# 3da.net
KiCad netlist of a schematic drawn in EAGLE
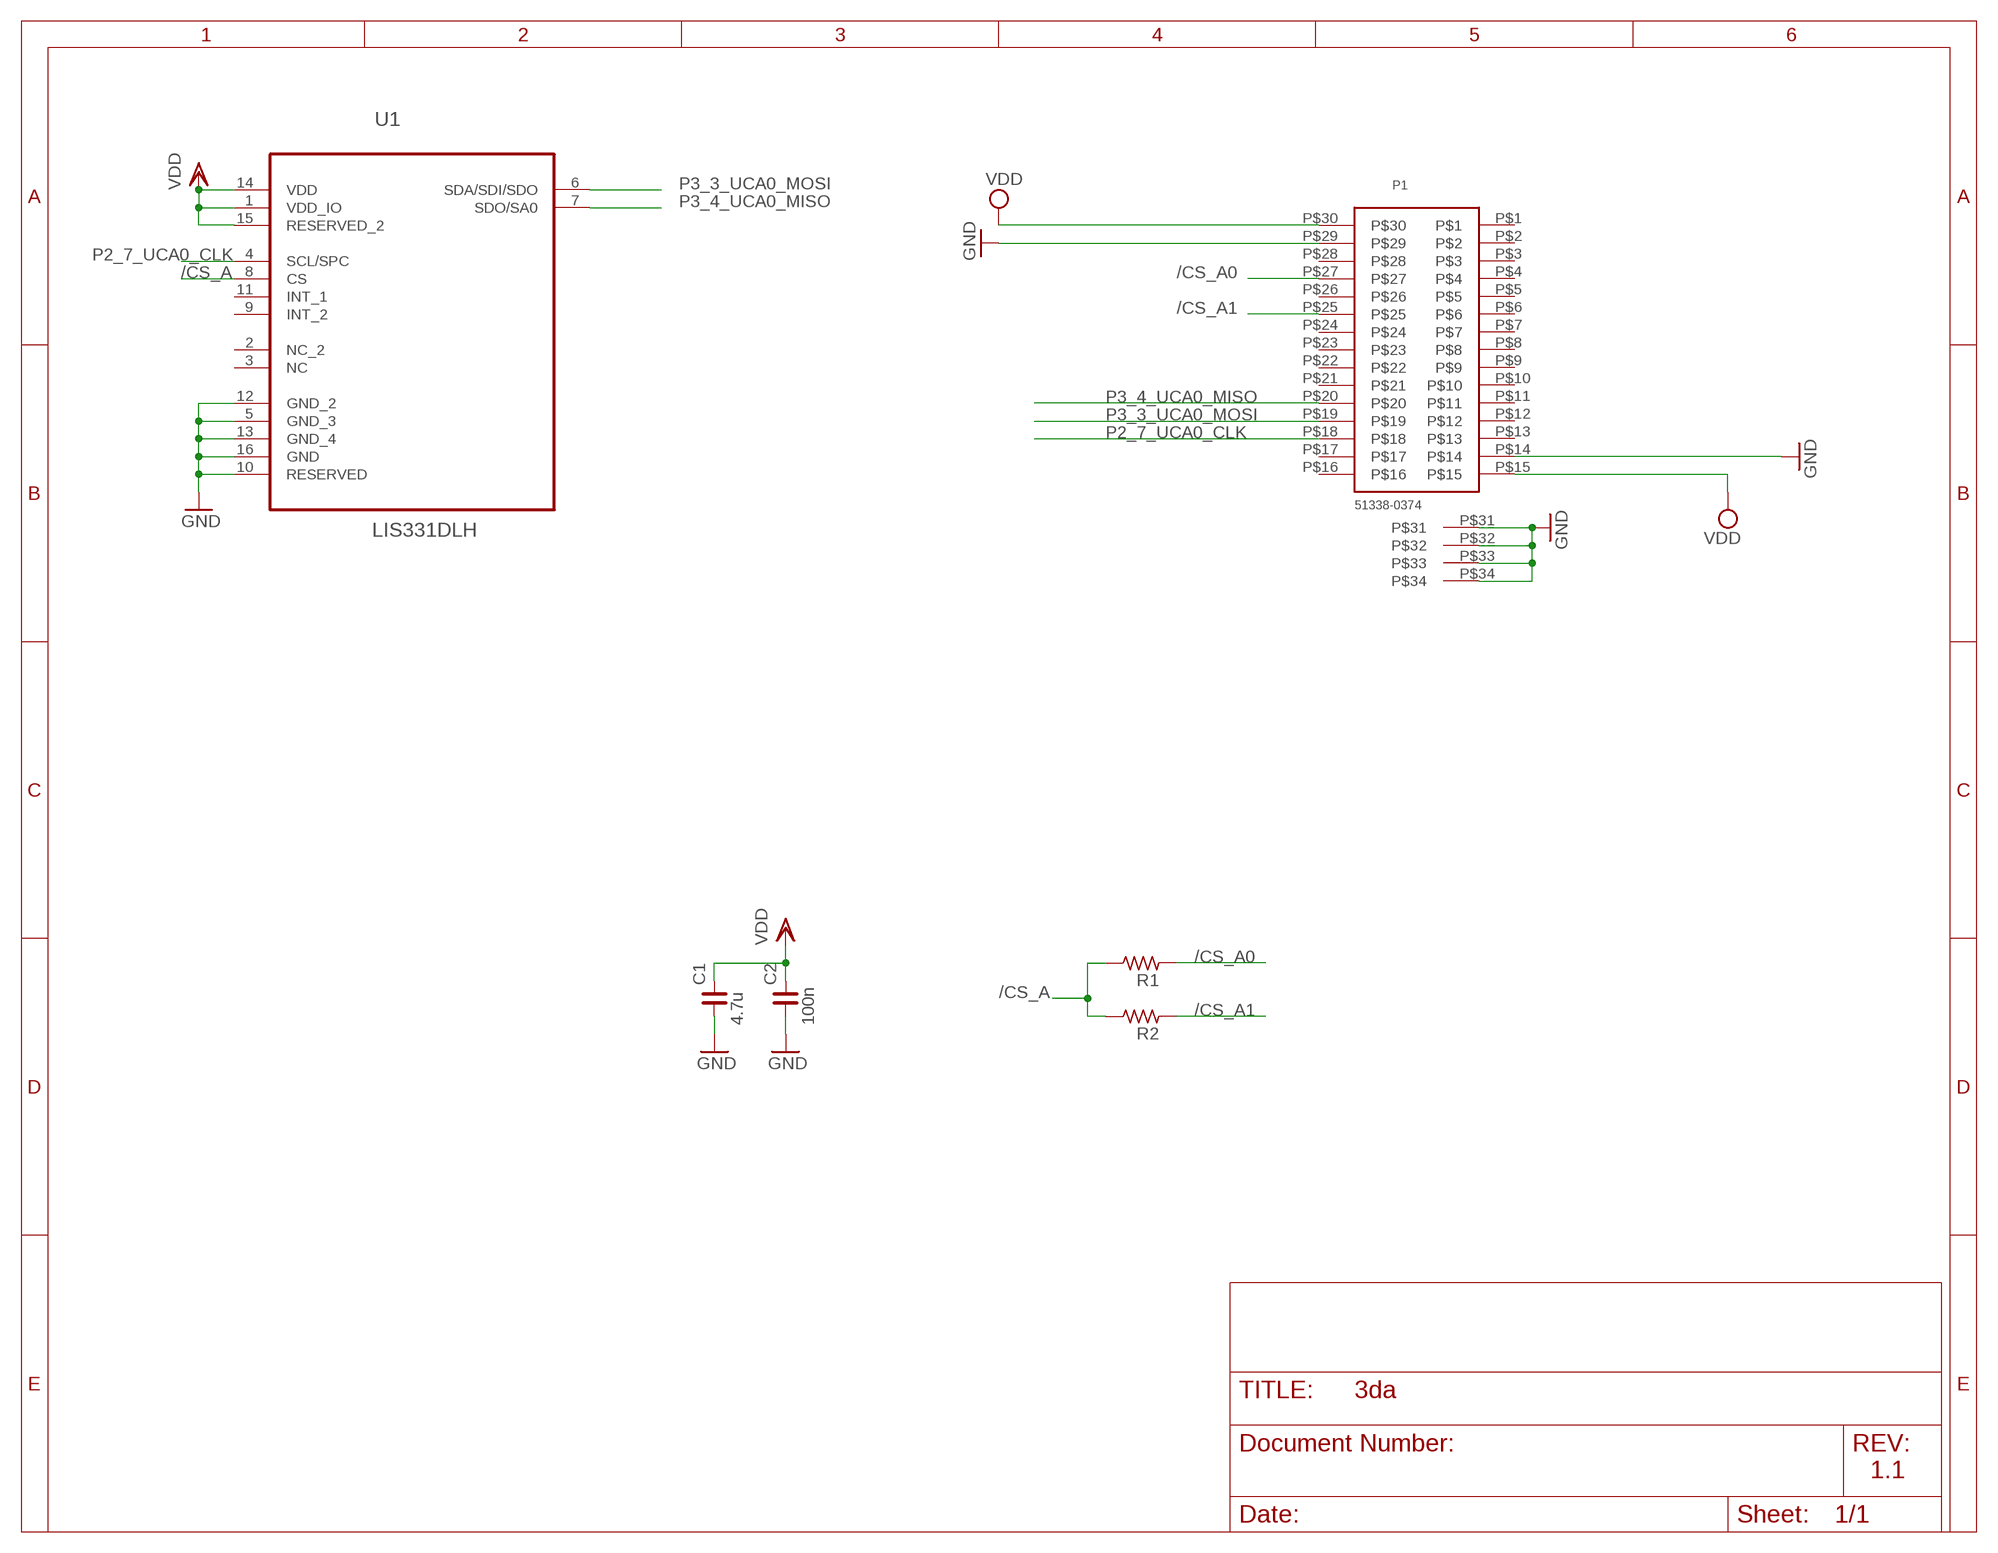
[diagram p0: schematic, sheet 1]

(export (version "E")
  (design (tool "Eeschema 10.0.6"))
  (components
    (comp (ref "C1")
      (value "4.7u")
      (footprint "eagle-import:C0402")
      (libsource (lib "eagle-import") (part "C_0402"))
    )
    (comp (ref "C2")
      (value "100n")
      (footprint "eagle-import:C0402")
      (libsource (lib "eagle-import") (part "C_0402"))
    )
    (comp (ref "P1")
      (value "51338-0374")
      (footprint "eagle-import:51338-0374_RECEPTACLE")
      (libsource (lib "eagle-import") (part "51338-0374_RECEPTACLE"))
    )
    (comp (ref "R1")
      (value "R_0402")
      (footprint "eagle-import:R0402")
      (libsource (lib "eagle-import") (part "R_0402"))
    )
    (comp (ref "R2")
      (value "R_0402")
      (footprint "eagle-import:R0402")
      (libsource (lib "eagle-import") (part "R_0402"))
    )
    (comp (ref "U1")
      (value "LIS331DLH")
      (footprint "eagle-import:LGA16R50P3X5_300X300X100")
      (libsource (lib "eagle-import") (part "LIS331DLH"))
    )
  )
  (nets
    (net (code "1") (name "/P2_7_UCA0_CLK") (class "Default")
      (node (ref "P1") (pin "P$18") (pinfunction "P$18_P$18") (pintype "bidirectional"))
      (node (ref "U1") (pin "4") (pinfunction "SCL/SPC_4") (pintype "input"))
    )
    (net (code "2") (name "/P3_3_UCA0_MOSI") (class "Default")
      (node (ref "P1") (pin "P$19") (pinfunction "P$19_P$19") (pintype "bidirectional"))
      (node (ref "U1") (pin "6") (pinfunction "SDA/SDI/SDO_6") (pintype "bidirectional"))
    )
    (net (code "3") (name "/P3_4_UCA0_MISO") (class "Default")
      (node (ref "P1") (pin "P$20") (pinfunction "P$20_P$20") (pintype "bidirectional"))
      (node (ref "U1") (pin "7") (pinfunction "SDO/SA0_7") (pintype "output"))
    )
    (net (code "4") (name "/{slash}CS_A") (class "Default")
      (node (ref "R1") (pin "2") (pinfunction "2_2") (pintype "passive"))
      (node (ref "R2") (pin "2") (pinfunction "2_2") (pintype "passive"))
      (node (ref "U1") (pin "8") (pinfunction "CS_8") (pintype "input"))
    )
    (net (code "5") (name "/{slash}CS_A0") (class "Default")
      (node (ref "P1") (pin "P$27") (pinfunction "P$27_P$27") (pintype "bidirectional"))
      (node (ref "R1") (pin "1") (pinfunction "1_1") (pintype "passive"))
    )
    (net (code "6") (name "/{slash}CS_A1") (class "Default")
      (node (ref "P1") (pin "P$25") (pinfunction "P$25_P$25") (pintype "bidirectional"))
      (node (ref "R2") (pin "1") (pinfunction "1_1") (pintype "passive"))
    )
    (net (code "7") (name "GND") (class "Default")
      (node (ref "C1") (pin "1") (pinfunction "1_1") (pintype "passive"))
      (node (ref "C2") (pin "1") (pinfunction "1_1") (pintype "passive"))
      (node (ref "P1") (pin "P$14") (pinfunction "P$14_P$14") (pintype "bidirectional"))
      (node (ref "P1") (pin "P$29") (pinfunction "P$29_P$29") (pintype "bidirectional"))
      (node (ref "P1") (pin "P$31") (pinfunction "P$31_P$31") (pintype "bidirectional"))
      (node (ref "P1") (pin "P$32") (pinfunction "P$32_P$32") (pintype "bidirectional"))
      (node (ref "P1") (pin "P$33") (pinfunction "P$33_P$33") (pintype "bidirectional"))
      (node (ref "P1") (pin "P$34") (pinfunction "P$34_P$34") (pintype "bidirectional"))
      (node (ref "U1") (pin "10") (pinfunction "RESERVED_10") (pintype "passive"))
      (node (ref "U1") (pin "12") (pinfunction "GND_2_12") (pintype "passive"))
      (node (ref "U1") (pin "13") (pinfunction "GND_4_13") (pintype "passive"))
      (node (ref "U1") (pin "16") (pinfunction "GND_16") (pintype "passive"))
      (node (ref "U1") (pin "5") (pinfunction "GND_3_5") (pintype "passive"))
    )
    (net (code "8") (name "VDD") (class "Default")
      (node (ref "C1") (pin "2") (pinfunction "2_2") (pintype "passive"))
      (node (ref "C2") (pin "2") (pinfunction "2_2") (pintype "passive"))
      (node (ref "P1") (pin "P$15") (pinfunction "P$15_P$15") (pintype "bidirectional"))
      (node (ref "P1") (pin "P$30") (pinfunction "P$30_P$30") (pintype "bidirectional"))
      (node (ref "U1") (pin "1") (pinfunction "VDD_IO_1") (pintype "power_in"))
      (node (ref "U1") (pin "14") (pinfunction "VDD_14") (pintype "power_in"))
      (node (ref "U1") (pin "15") (pinfunction "RESERVED_2_15") (pintype "power_in"))
    )
    (net (code "9") (name "unconnected-(P1-PadP$1)") (class "Default")
      (node (ref "P1") (pin "P$1") (pinfunction "P$1_P$1") (pintype "bidirectional"))
    )
    (net (code "10") (name "unconnected-(P1-PadP$2)") (class "Default")
      (node (ref "P1") (pin "P$2") (pinfunction "P$2_P$2") (pintype "bidirectional"))
    )
    (net (code "11") (name "unconnected-(P1-PadP$3)") (class "Default")
      (node (ref "P1") (pin "P$3") (pinfunction "P$3_P$3") (pintype "bidirectional"))
    )
    (net (code "12") (name "unconnected-(P1-PadP$4)") (class "Default")
      (node (ref "P1") (pin "P$4") (pinfunction "P$4_P$4") (pintype "bidirectional"))
    )
    (net (code "13") (name "unconnected-(P1-PadP$5)") (class "Default")
      (node (ref "P1") (pin "P$5") (pinfunction "P$5_P$5") (pintype "bidirectional"))
    )
    (net (code "14") (name "unconnected-(P1-PadP$6)") (class "Default")
      (node (ref "P1") (pin "P$6") (pinfunction "P$6_P$6") (pintype "bidirectional"))
    )
    (net (code "15") (name "unconnected-(P1-PadP$7)") (class "Default")
      (node (ref "P1") (pin "P$7") (pinfunction "P$7_P$7") (pintype "bidirectional"))
    )
    (net (code "16") (name "unconnected-(P1-PadP$8)") (class "Default")
      (node (ref "P1") (pin "P$8") (pinfunction "P$8_P$8") (pintype "bidirectional"))
    )
    (net (code "17") (name "unconnected-(P1-PadP$9)") (class "Default")
      (node (ref "P1") (pin "P$9") (pinfunction "P$9_P$9") (pintype "bidirectional"))
    )
    (net (code "18") (name "unconnected-(P1-PadP$10)") (class "Default")
      (node (ref "P1") (pin "P$10") (pinfunction "P$10_P$10") (pintype "bidirectional"))
    )
    (net (code "19") (name "unconnected-(P1-PadP$11)") (class "Default")
      (node (ref "P1") (pin "P$11") (pinfunction "P$11_P$11") (pintype "bidirectional"))
    )
    (net (code "20") (name "unconnected-(P1-PadP$12)") (class "Default")
      (node (ref "P1") (pin "P$12") (pinfunction "P$12_P$12") (pintype "bidirectional"))
    )
    (net (code "21") (name "unconnected-(P1-PadP$13)") (class "Default")
      (node (ref "P1") (pin "P$13") (pinfunction "P$13_P$13") (pintype "bidirectional"))
    )
    (net (code "22") (name "unconnected-(P1-PadP$16)") (class "Default")
      (node (ref "P1") (pin "P$16") (pinfunction "P$16_P$16") (pintype "bidirectional"))
    )
    (net (code "23") (name "unconnected-(P1-PadP$17)") (class "Default")
      (node (ref "P1") (pin "P$17") (pinfunction "P$17_P$17") (pintype "bidirectional"))
    )
    (net (code "24") (name "unconnected-(P1-PadP$21)") (class "Default")
      (node (ref "P1") (pin "P$21") (pinfunction "P$21_P$21") (pintype "bidirectional"))
    )
    (net (code "25") (name "unconnected-(P1-PadP$22)") (class "Default")
      (node (ref "P1") (pin "P$22") (pinfunction "P$22_P$22") (pintype "bidirectional"))
    )
    (net (code "26") (name "unconnected-(P1-PadP$23)") (class "Default")
      (node (ref "P1") (pin "P$23") (pinfunction "P$23_P$23") (pintype "bidirectional"))
    )
    (net (code "27") (name "unconnected-(P1-PadP$24)") (class "Default")
      (node (ref "P1") (pin "P$24") (pinfunction "P$24_P$24") (pintype "bidirectional"))
    )
    (net (code "28") (name "unconnected-(P1-PadP$26)") (class "Default")
      (node (ref "P1") (pin "P$26") (pinfunction "P$26_P$26") (pintype "bidirectional"))
    )
    (net (code "29") (name "unconnected-(P1-PadP$28)") (class "Default")
      (node (ref "P1") (pin "P$28") (pinfunction "P$28_P$28") (pintype "bidirectional"))
    )
    (net (code "30") (name "unconnected-(U1-INT_1-Pad11)") (class "Default")
      (node (ref "U1") (pin "11") (pinfunction "INT_1_11") (pintype "input"))
    )
    (net (code "31") (name "unconnected-(U1-INT_2-Pad9)") (class "Default")
      (node (ref "U1") (pin "9") (pinfunction "INT_2_9") (pintype "input"))
    )
    (net (code "32") (name "unconnected-(U1-NC-Pad3)") (class "Default")
      (node (ref "U1") (pin "3") (pinfunction "NC_3") (pintype "no_connect"))
    )
    (net (code "33") (name "unconnected-(U1-NC_2-Pad2)") (class "Default")
      (node (ref "U1") (pin "2") (pinfunction "NC_2_2") (pintype "no_connect"))
    )
  )
)
